# Dual6X03.net
KiCad netlist of a schematic drawn in EAGLE
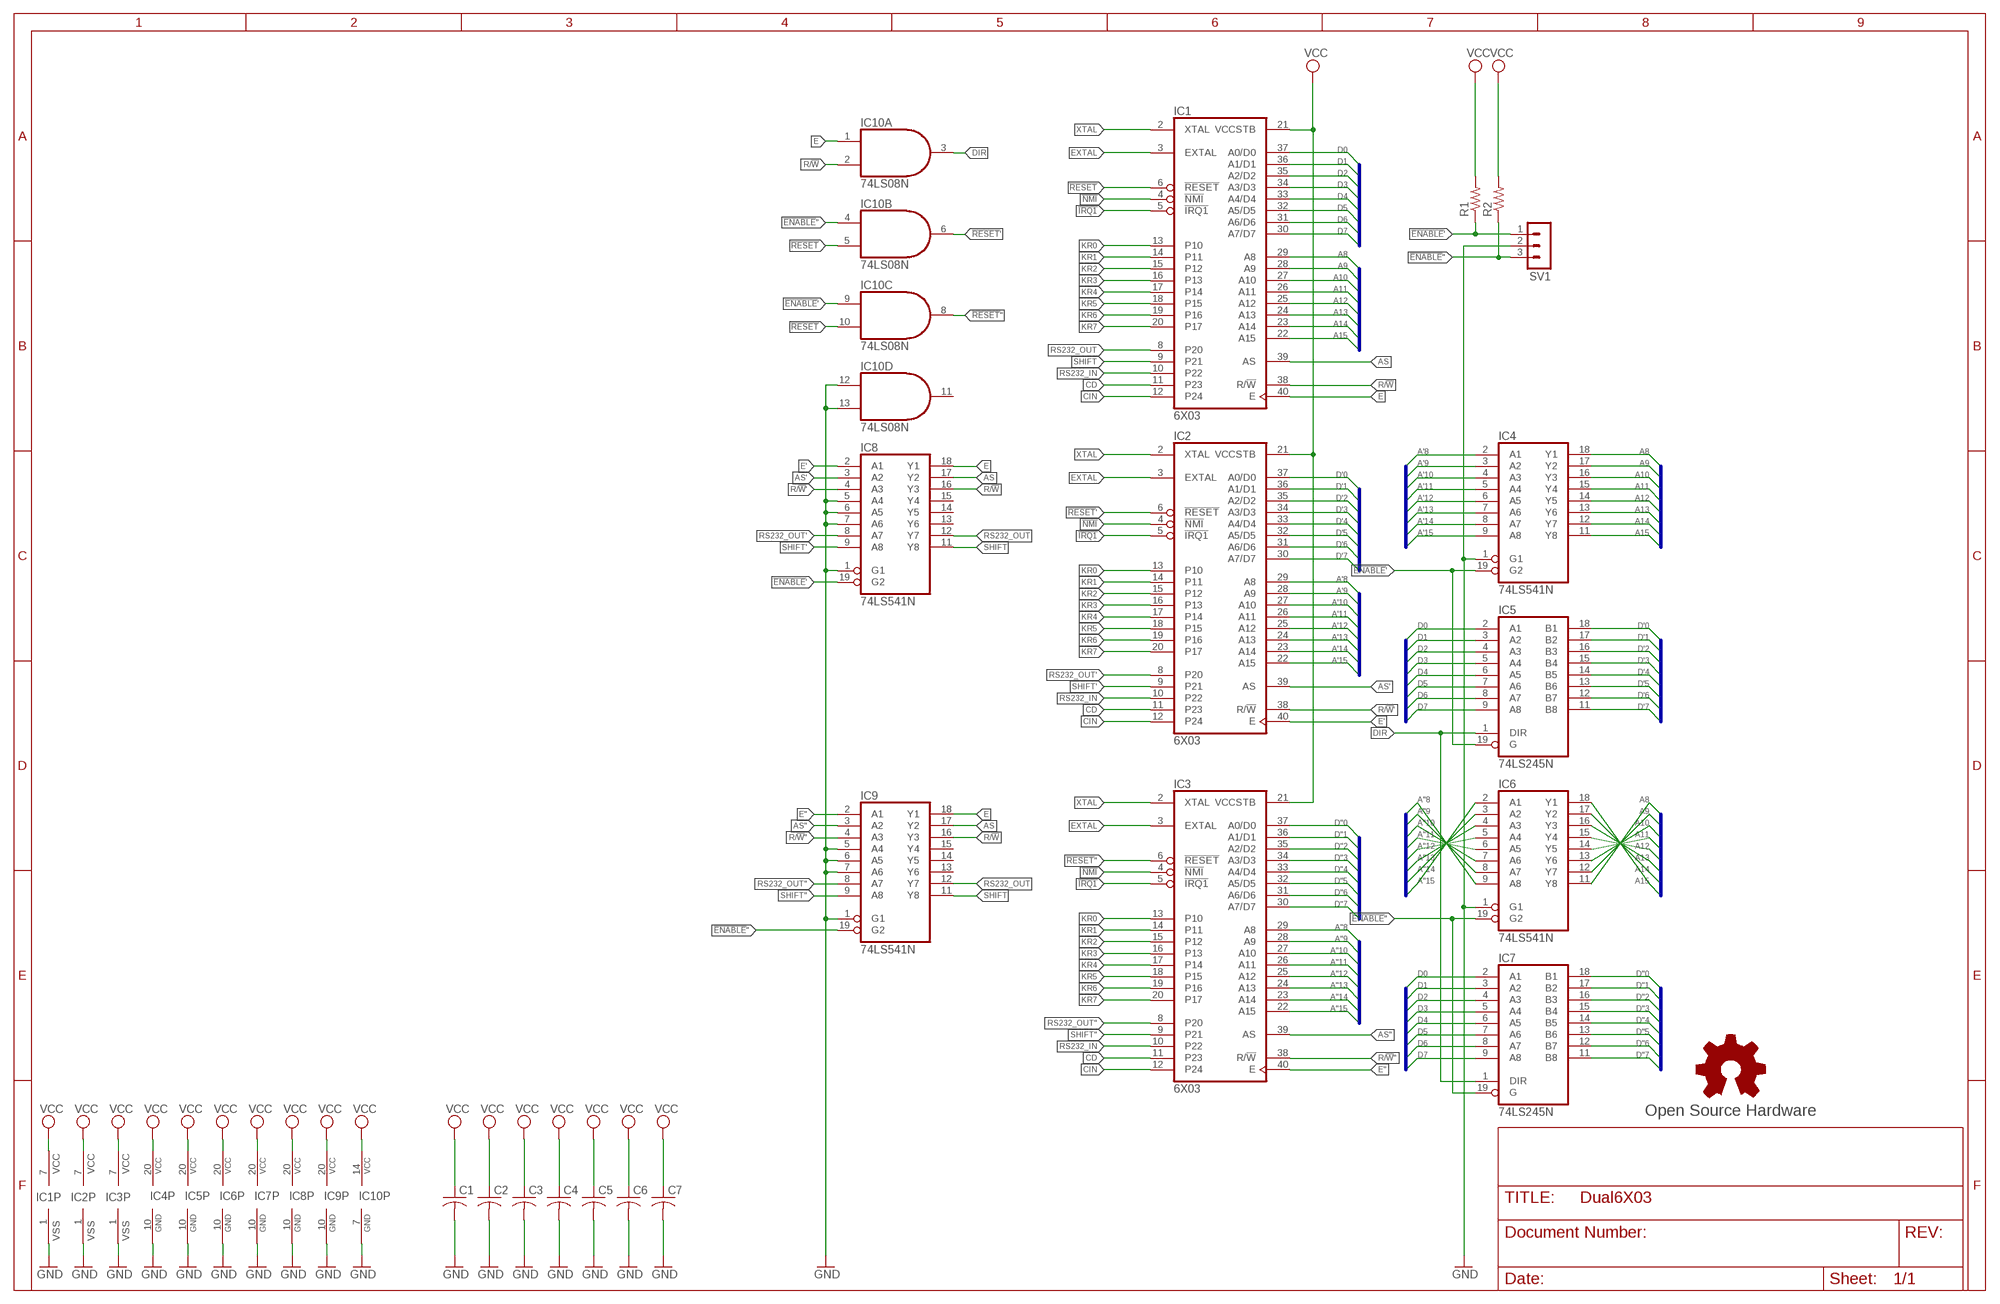
[diagram p0: schematic, sheet 1]

(export (version "E")
  (design (tool "Eeschema 10.0.6"))
  (components
    (comp (ref "C1")
      (value "C-US025-025X050")
      (footprint "eagle-import:C025-025X050")
      (libsource (lib "eagle-import") (part "C-US025-025X050"))
    )
    (comp (ref "C2")
      (value "C-US025-025X050")
      (footprint "eagle-import:C025-025X050")
      (libsource (lib "eagle-import") (part "C-US025-025X050"))
    )
    (comp (ref "C3")
      (value "C-US025-025X050")
      (footprint "eagle-import:C025-025X050")
      (libsource (lib "eagle-import") (part "C-US025-025X050"))
    )
    (comp (ref "C4")
      (value "C-US025-025X050")
      (footprint "eagle-import:C025-025X050")
      (libsource (lib "eagle-import") (part "C-US025-025X050"))
    )
    (comp (ref "C5")
      (value "C-US025-025X050")
      (footprint "eagle-import:C025-025X050")
      (libsource (lib "eagle-import") (part "C-US025-025X050"))
    )
    (comp (ref "C6")
      (value "C-US025-025X050")
      (footprint "eagle-import:C025-025X050")
      (libsource (lib "eagle-import") (part "C-US025-025X050"))
    )
    (comp (ref "C7")
      (value "C-US025-025X050")
      (footprint "eagle-import:C025-025X050")
      (libsource (lib "eagle-import") (part "C-US025-025X050"))
    )
    (comp (ref "GOLD_ORB_SM1")
      (value "Open Source Hardware")
      (footprint "eagle-import:OSHW_8MM")
      (libsource (lib "eagle-import") (part "OSHWLOGOLOGO8MM"))
    )
    (comp (ref "IC1")
      (value "6X03")
      (footprint "eagle-import:DIL40-ROUNDPAD")
      (libsource (lib "eagle-import") (part "6801EMR"))
    )
    (comp (ref "IC2")
      (value "6X03")
      (footprint "eagle-import:DIL40-ROUNDPAD")
      (libsource (lib "eagle-import") (part "6801EMR"))
    )
    (comp (ref "IC3")
      (value "6X03")
      (footprint "eagle-import:DIL40-ROUNDPAD")
      (libsource (lib "eagle-import") (part "6801EMR"))
    )
    (comp (ref "IC4")
      (value "74LS541N")
      (footprint "eagle-import:DIL20")
      (libsource (lib "eagle-import") (part "74541NLS"))
    )
    (comp (ref "IC5")
      (value "74LS245N")
      (footprint "eagle-import:DIL20")
      (libsource (lib "eagle-import") (part "74245NLS"))
    )
    (comp (ref "IC6")
      (value "74LS541N")
      (footprint "eagle-import:DIL20")
      (libsource (lib "eagle-import") (part "74541NLS"))
    )
    (comp (ref "IC7")
      (value "74LS245N")
      (footprint "eagle-import:DIL20")
      (libsource (lib "eagle-import") (part "74245NLS"))
    )
    (comp (ref "IC8")
      (value "74LS541N")
      (footprint "eagle-import:DIL20")
      (libsource (lib "eagle-import") (part "74541NLS"))
    )
    (comp (ref "IC9")
      (value "74LS541N")
      (footprint "eagle-import:DIL20")
      (libsource (lib "eagle-import") (part "74541NLS"))
    )
    (comp (ref "IC10")
      (value "74LS08N")
      (footprint "eagle-import:DIL14")
      (libsource (lib "eagle-import") (part "7408NLS"))
    )
    (comp (ref "R1")
      (value "R-US_0204/2V")
      (footprint "eagle-import:0204V")
      (libsource (lib "eagle-import") (part "R-US_0204/2V"))
    )
    (comp (ref "R2")
      (value "R-US_0204/2V")
      (footprint "eagle-import:0204V")
      (libsource (lib "eagle-import") (part "R-US_0204/2V"))
    )
    (comp (ref "SV1")
      (value "MA03-1")
      (footprint "eagle-import:MA03-1")
      (libsource (lib "eagle-import") (part "MA03-1"))
    )
  )
  (nets
    (net (code "1") (name "/A''8") (class "Default")
      (node (ref "IC3") (pin "29") (pinfunction "A8_29") (pintype "bidirectional"))
      (node (ref "IC6") (pin "9") (pinfunction "A8_9") (pintype "input"))
    )
    (net (code "2") (name "/A''9") (class "Default")
      (node (ref "IC3") (pin "28") (pinfunction "A9_28") (pintype "bidirectional"))
      (node (ref "IC6") (pin "8") (pinfunction "A7_8") (pintype "input"))
    )
    (net (code "3") (name "/A''10") (class "Default")
      (node (ref "IC3") (pin "27") (pinfunction "A10_27") (pintype "bidirectional"))
      (node (ref "IC6") (pin "7") (pinfunction "A6_7") (pintype "input"))
    )
    (net (code "4") (name "/A''11") (class "Default")
      (node (ref "IC3") (pin "26") (pinfunction "A11_26") (pintype "bidirectional"))
      (node (ref "IC6") (pin "6") (pinfunction "A5_6") (pintype "input"))
    )
    (net (code "5") (name "/A''12") (class "Default")
      (node (ref "IC3") (pin "25") (pinfunction "A12_25") (pintype "bidirectional"))
      (node (ref "IC6") (pin "5") (pinfunction "A4_5") (pintype "input"))
    )
    (net (code "6") (name "/A''13") (class "Default")
      (node (ref "IC3") (pin "24") (pinfunction "A13_24") (pintype "bidirectional"))
      (node (ref "IC6") (pin "4") (pinfunction "A3_4") (pintype "input"))
    )
    (net (code "7") (name "/A''14") (class "Default")
      (node (ref "IC3") (pin "23") (pinfunction "A14_23") (pintype "bidirectional"))
      (node (ref "IC6") (pin "3") (pinfunction "A2_3") (pintype "input"))
    )
    (net (code "8") (name "/A''15") (class "Default")
      (node (ref "IC3") (pin "22") (pinfunction "A15_22") (pintype "bidirectional"))
      (node (ref "IC6") (pin "2") (pinfunction "A1_2") (pintype "input"))
    )
    (net (code "9") (name "/A'8") (class "Default")
      (node (ref "IC2") (pin "29") (pinfunction "A8_29") (pintype "bidirectional"))
      (node (ref "IC4") (pin "2") (pinfunction "A1_2") (pintype "input"))
    )
    (net (code "10") (name "/A'9") (class "Default")
      (node (ref "IC2") (pin "28") (pinfunction "A9_28") (pintype "bidirectional"))
      (node (ref "IC4") (pin "3") (pinfunction "A2_3") (pintype "input"))
    )
    (net (code "11") (name "/A'10") (class "Default")
      (node (ref "IC2") (pin "27") (pinfunction "A10_27") (pintype "bidirectional"))
      (node (ref "IC4") (pin "4") (pinfunction "A3_4") (pintype "input"))
    )
    (net (code "12") (name "/A'11") (class "Default")
      (node (ref "IC2") (pin "26") (pinfunction "A11_26") (pintype "bidirectional"))
      (node (ref "IC4") (pin "5") (pinfunction "A4_5") (pintype "input"))
    )
    (net (code "13") (name "/A'12") (class "Default")
      (node (ref "IC2") (pin "25") (pinfunction "A12_25") (pintype "bidirectional"))
      (node (ref "IC4") (pin "6") (pinfunction "A5_6") (pintype "input"))
    )
    (net (code "14") (name "/A'13") (class "Default")
      (node (ref "IC2") (pin "24") (pinfunction "A13_24") (pintype "bidirectional"))
      (node (ref "IC4") (pin "7") (pinfunction "A6_7") (pintype "input"))
    )
    (net (code "15") (name "/A'14") (class "Default")
      (node (ref "IC2") (pin "23") (pinfunction "A14_23") (pintype "bidirectional"))
      (node (ref "IC4") (pin "8") (pinfunction "A7_8") (pintype "input"))
    )
    (net (code "16") (name "/A'15") (class "Default")
      (node (ref "IC2") (pin "22") (pinfunction "A15_22") (pintype "bidirectional"))
      (node (ref "IC4") (pin "9") (pinfunction "A8_9") (pintype "input"))
    )
    (net (code "17") (name "/A8") (class "Default")
      (node (ref "IC1") (pin "29") (pinfunction "A8_29") (pintype "bidirectional"))
      (node (ref "IC4") (pin "18") (pinfunction "Y1_18") (pintype "tri_state"))
      (node (ref "IC6") (pin "11") (pinfunction "Y8_11") (pintype "tri_state"))
    )
    (net (code "18") (name "/A9") (class "Default")
      (node (ref "IC1") (pin "28") (pinfunction "A9_28") (pintype "bidirectional"))
      (node (ref "IC4") (pin "17") (pinfunction "Y2_17") (pintype "tri_state"))
      (node (ref "IC6") (pin "12") (pinfunction "Y7_12") (pintype "tri_state"))
    )
    (net (code "19") (name "/A10") (class "Default")
      (node (ref "IC1") (pin "27") (pinfunction "A10_27") (pintype "bidirectional"))
      (node (ref "IC4") (pin "16") (pinfunction "Y3_16") (pintype "tri_state"))
      (node (ref "IC6") (pin "13") (pinfunction "Y6_13") (pintype "tri_state"))
    )
    (net (code "20") (name "/A11") (class "Default")
      (node (ref "IC1") (pin "26") (pinfunction "A11_26") (pintype "bidirectional"))
      (node (ref "IC4") (pin "15") (pinfunction "Y4_15") (pintype "tri_state"))
      (node (ref "IC6") (pin "14") (pinfunction "Y5_14") (pintype "tri_state"))
    )
    (net (code "21") (name "/A12") (class "Default")
      (node (ref "IC1") (pin "25") (pinfunction "A12_25") (pintype "bidirectional"))
      (node (ref "IC4") (pin "14") (pinfunction "Y5_14") (pintype "tri_state"))
      (node (ref "IC6") (pin "15") (pinfunction "Y4_15") (pintype "tri_state"))
    )
    (net (code "22") (name "/A13") (class "Default")
      (node (ref "IC1") (pin "24") (pinfunction "A13_24") (pintype "bidirectional"))
      (node (ref "IC4") (pin "13") (pinfunction "Y6_13") (pintype "tri_state"))
      (node (ref "IC6") (pin "16") (pinfunction "Y3_16") (pintype "tri_state"))
    )
    (net (code "23") (name "/A14") (class "Default")
      (node (ref "IC1") (pin "23") (pinfunction "A14_23") (pintype "bidirectional"))
      (node (ref "IC4") (pin "12") (pinfunction "Y7_12") (pintype "tri_state"))
      (node (ref "IC6") (pin "17") (pinfunction "Y2_17") (pintype "tri_state"))
    )
    (net (code "24") (name "/A15") (class "Default")
      (node (ref "IC1") (pin "22") (pinfunction "A15_22") (pintype "bidirectional"))
      (node (ref "IC4") (pin "11") (pinfunction "Y8_11") (pintype "tri_state"))
      (node (ref "IC6") (pin "18") (pinfunction "Y1_18") (pintype "tri_state"))
    )
    (net (code "25") (name "/D''0") (class "Default")
      (node (ref "IC3") (pin "37") (pinfunction "A0/D0_37") (pintype "bidirectional"))
      (node (ref "IC7") (pin "18") (pinfunction "B1_18") (pintype "bidirectional"))
    )
    (net (code "26") (name "/D''1") (class "Default")
      (node (ref "IC3") (pin "36") (pinfunction "A1/D1_36") (pintype "bidirectional"))
      (node (ref "IC7") (pin "17") (pinfunction "B2_17") (pintype "bidirectional"))
    )
    (net (code "27") (name "/D''2") (class "Default")
      (node (ref "IC3") (pin "35") (pinfunction "A2/D2_35") (pintype "bidirectional"))
      (node (ref "IC7") (pin "16") (pinfunction "B3_16") (pintype "bidirectional"))
    )
    (net (code "28") (name "/D''3") (class "Default")
      (node (ref "IC3") (pin "34") (pinfunction "A3/D3_34") (pintype "bidirectional"))
      (node (ref "IC7") (pin "15") (pinfunction "B4_15") (pintype "bidirectional"))
    )
    (net (code "29") (name "/D''4") (class "Default")
      (node (ref "IC3") (pin "33") (pinfunction "A4/D4_33") (pintype "bidirectional"))
      (node (ref "IC7") (pin "14") (pinfunction "B5_14") (pintype "bidirectional"))
    )
    (net (code "30") (name "/D''5") (class "Default")
      (node (ref "IC3") (pin "32") (pinfunction "A5/D5_32") (pintype "bidirectional"))
      (node (ref "IC7") (pin "13") (pinfunction "B6_13") (pintype "bidirectional"))
    )
    (net (code "31") (name "/D''6") (class "Default")
      (node (ref "IC3") (pin "31") (pinfunction "A6/D6_31") (pintype "bidirectional"))
      (node (ref "IC7") (pin "12") (pinfunction "B7_12") (pintype "bidirectional"))
    )
    (net (code "32") (name "/D''7") (class "Default")
      (node (ref "IC3") (pin "30") (pinfunction "A7/D7_30") (pintype "bidirectional"))
      (node (ref "IC7") (pin "11") (pinfunction "B8_11") (pintype "bidirectional"))
    )
    (net (code "33") (name "/D'0") (class "Default")
      (node (ref "IC2") (pin "37") (pinfunction "A0/D0_37") (pintype "bidirectional"))
      (node (ref "IC5") (pin "18") (pinfunction "B1_18") (pintype "bidirectional"))
    )
    (net (code "34") (name "/D'1") (class "Default")
      (node (ref "IC2") (pin "36") (pinfunction "A1/D1_36") (pintype "bidirectional"))
      (node (ref "IC5") (pin "17") (pinfunction "B2_17") (pintype "bidirectional"))
    )
    (net (code "35") (name "/D'2") (class "Default")
      (node (ref "IC2") (pin "35") (pinfunction "A2/D2_35") (pintype "bidirectional"))
      (node (ref "IC5") (pin "16") (pinfunction "B3_16") (pintype "bidirectional"))
    )
    (net (code "36") (name "/D'3") (class "Default")
      (node (ref "IC2") (pin "34") (pinfunction "A3/D3_34") (pintype "bidirectional"))
      (node (ref "IC5") (pin "15") (pinfunction "B4_15") (pintype "bidirectional"))
    )
    (net (code "37") (name "/D'4") (class "Default")
      (node (ref "IC2") (pin "33") (pinfunction "A4/D4_33") (pintype "bidirectional"))
      (node (ref "IC5") (pin "14") (pinfunction "B5_14") (pintype "bidirectional"))
    )
    (net (code "38") (name "/D'5") (class "Default")
      (node (ref "IC2") (pin "32") (pinfunction "A5/D5_32") (pintype "bidirectional"))
      (node (ref "IC5") (pin "13") (pinfunction "B6_13") (pintype "bidirectional"))
    )
    (net (code "39") (name "/D'6") (class "Default")
      (node (ref "IC2") (pin "31") (pinfunction "A6/D6_31") (pintype "bidirectional"))
      (node (ref "IC5") (pin "12") (pinfunction "B7_12") (pintype "bidirectional"))
    )
    (net (code "40") (name "/D'7") (class "Default")
      (node (ref "IC2") (pin "30") (pinfunction "A7/D7_30") (pintype "bidirectional"))
      (node (ref "IC5") (pin "11") (pinfunction "B8_11") (pintype "bidirectional"))
    )
    (net (code "41") (name "/D0") (class "Default")
      (node (ref "IC1") (pin "37") (pinfunction "A0/D0_37") (pintype "bidirectional"))
      (node (ref "IC5") (pin "2") (pinfunction "A1_2") (pintype "bidirectional"))
      (node (ref "IC7") (pin "2") (pinfunction "A1_2") (pintype "bidirectional"))
    )
    (net (code "42") (name "/D1") (class "Default")
      (node (ref "IC1") (pin "36") (pinfunction "A1/D1_36") (pintype "bidirectional"))
      (node (ref "IC5") (pin "3") (pinfunction "A2_3") (pintype "bidirectional"))
      (node (ref "IC7") (pin "3") (pinfunction "A2_3") (pintype "bidirectional"))
    )
    (net (code "43") (name "/D2") (class "Default")
      (node (ref "IC1") (pin "35") (pinfunction "A2/D2_35") (pintype "bidirectional"))
      (node (ref "IC5") (pin "4") (pinfunction "A3_4") (pintype "bidirectional"))
      (node (ref "IC7") (pin "4") (pinfunction "A3_4") (pintype "bidirectional"))
    )
    (net (code "44") (name "/D3") (class "Default")
      (node (ref "IC1") (pin "34") (pinfunction "A3/D3_34") (pintype "bidirectional"))
      (node (ref "IC5") (pin "5") (pinfunction "A4_5") (pintype "bidirectional"))
      (node (ref "IC7") (pin "5") (pinfunction "A4_5") (pintype "bidirectional"))
    )
    (net (code "45") (name "/D4") (class "Default")
      (node (ref "IC1") (pin "33") (pinfunction "A4/D4_33") (pintype "bidirectional"))
      (node (ref "IC5") (pin "6") (pinfunction "A5_6") (pintype "bidirectional"))
      (node (ref "IC7") (pin "6") (pinfunction "A5_6") (pintype "bidirectional"))
    )
    (net (code "46") (name "/D5") (class "Default")
      (node (ref "IC1") (pin "32") (pinfunction "A5/D5_32") (pintype "bidirectional"))
      (node (ref "IC5") (pin "7") (pinfunction "A6_7") (pintype "bidirectional"))
      (node (ref "IC7") (pin "7") (pinfunction "A6_7") (pintype "bidirectional"))
    )
    (net (code "47") (name "/D6") (class "Default")
      (node (ref "IC1") (pin "31") (pinfunction "A6/D6_31") (pintype "bidirectional"))
      (node (ref "IC5") (pin "8") (pinfunction "A7_8") (pintype "bidirectional"))
      (node (ref "IC7") (pin "8") (pinfunction "A7_8") (pintype "bidirectional"))
    )
    (net (code "48") (name "/D7") (class "Default")
      (node (ref "IC1") (pin "30") (pinfunction "A7/D7_30") (pintype "bidirectional"))
      (node (ref "IC5") (pin "9") (pinfunction "A8_9") (pintype "bidirectional"))
      (node (ref "IC7") (pin "9") (pinfunction "A8_9") (pintype "bidirectional"))
    )
    (net (code "49") (name "/R{slash}~{W}") (class "Default")
      (node (ref "IC1") (pin "38") (pinfunction "R/~{W}_38") (pintype "output"))
      (node (ref "IC10") (pin "2") (pinfunction "I1_2") (pintype "input"))
      (node (ref "IC8") (pin "16") (pinfunction "Y3_16") (pintype "tri_state"))
      (node (ref "IC9") (pin "16") (pinfunction "Y3_16") (pintype "tri_state"))
    )
    (net (code "50") (name "/R{slash}~{W}'") (class "Default")
      (node (ref "IC2") (pin "38") (pinfunction "R/~{W}_38") (pintype "output"))
      (node (ref "IC8") (pin "4") (pinfunction "A3_4") (pintype "input"))
    )
    (net (code "51") (name "/R{slash}~{W}''") (class "Default")
      (node (ref "IC3") (pin "38") (pinfunction "R/~{W}_38") (pintype "output"))
      (node (ref "IC9") (pin "4") (pinfunction "A3_4") (pintype "input"))
    )
    (net (code "52") (name "/~{ENABLE}'") (class "Default")
      (node (ref "IC10") (pin "9") (pinfunction "I0_9") (pintype "input"))
      (node (ref "IC4") (pin "19") (pinfunction "G2_19") (pintype "input"))
      (node (ref "IC5") (pin "19") (pinfunction "G_19") (pintype "input"))
      (node (ref "IC8") (pin "19") (pinfunction "G2_19") (pintype "input"))
      (node (ref "R1") (pin "1") (pinfunction "1_1") (pintype "passive"))
      (node (ref "SV1") (pin "1") (pinfunction "1_1") (pintype "passive"))
    )
    (net (code "53") (name "/~{ENABLE}''") (class "Default")
      (node (ref "IC10") (pin "4") (pinfunction "I0_4") (pintype "input"))
      (node (ref "IC6") (pin "19") (pinfunction "G2_19") (pintype "input"))
      (node (ref "IC7") (pin "19") (pinfunction "G_19") (pintype "input"))
      (node (ref "IC9") (pin "19") (pinfunction "G2_19") (pintype "input"))
      (node (ref "R2") (pin "1") (pinfunction "1_1") (pintype "passive"))
      (node (ref "SV1") (pin "3") (pinfunction "3_3") (pintype "passive"))
    )
    (net (code "54") (name "/~{IRQ1}") (class "Default")
      (node (ref "IC1") (pin "5") (pinfunction "~{IRQ1}_5") (pintype "input"))
      (node (ref "IC2") (pin "5") (pinfunction "~{IRQ1}_5") (pintype "input"))
      (node (ref "IC3") (pin "5") (pinfunction "~{IRQ1}_5") (pintype "input"))
    )
    (net (code "55") (name "/~{NMI}") (class "Default")
      (node (ref "IC1") (pin "4") (pinfunction "~{NMI}_4") (pintype "input"))
      (node (ref "IC2") (pin "4") (pinfunction "~{NMI}_4") (pintype "input"))
      (node (ref "IC3") (pin "4") (pinfunction "~{NMI}_4") (pintype "input"))
    )
    (net (code "56") (name "/~{RESET}") (class "Default")
      (node (ref "IC1") (pin "6") (pinfunction "~{RESET}_6") (pintype "input"))
      (node (ref "IC10") (pin "10") (pinfunction "I1_10") (pintype "input"))
      (node (ref "IC10") (pin "5") (pinfunction "I1_5") (pintype "input"))
    )
    (net (code "57") (name "/~{RESET}'") (class "Default")
      (node (ref "IC10") (pin "6") (pinfunction "O_6") (pintype "output"))
      (node (ref "IC2") (pin "6") (pinfunction "~{RESET}_6") (pintype "input"))
    )
    (net (code "58") (name "/~{RESET}''") (class "Default")
      (node (ref "IC10") (pin "8") (pinfunction "O_8") (pintype "output"))
      (node (ref "IC3") (pin "6") (pinfunction "~{RESET}_6") (pintype "input"))
    )
    (net (code "59") (name "AS") (class "Default")
      (node (ref "IC1") (pin "39") (pinfunction "AS_39") (pintype "bidirectional"))
      (node (ref "IC8") (pin "17") (pinfunction "Y2_17") (pintype "tri_state"))
      (node (ref "IC9") (pin "17") (pinfunction "Y2_17") (pintype "tri_state"))
    )
    (net (code "60") (name "AS'") (class "Default")
      (node (ref "IC2") (pin "39") (pinfunction "AS_39") (pintype "bidirectional"))
      (node (ref "IC8") (pin "3") (pinfunction "A2_3") (pintype "input"))
    )
    (net (code "61") (name "AS''") (class "Default")
      (node (ref "IC3") (pin "39") (pinfunction "AS_39") (pintype "bidirectional"))
      (node (ref "IC9") (pin "3") (pinfunction "A2_3") (pintype "input"))
    )
    (net (code "62") (name "CD") (class "Default")
      (node (ref "IC1") (pin "11") (pinfunction "P23_11") (pintype "bidirectional"))
      (node (ref "IC2") (pin "11") (pinfunction "P23_11") (pintype "bidirectional"))
      (node (ref "IC3") (pin "11") (pinfunction "P23_11") (pintype "bidirectional"))
    )
    (net (code "63") (name "CIN") (class "Default")
      (node (ref "IC1") (pin "12") (pinfunction "P24_12") (pintype "bidirectional"))
      (node (ref "IC2") (pin "12") (pinfunction "P24_12") (pintype "bidirectional"))
      (node (ref "IC3") (pin "12") (pinfunction "P24_12") (pintype "bidirectional"))
    )
    (net (code "64") (name "DIR") (class "Default")
      (node (ref "IC10") (pin "3") (pinfunction "O_3") (pintype "output"))
      (node (ref "IC5") (pin "1") (pinfunction "DIR_1") (pintype "input"))
      (node (ref "IC7") (pin "1") (pinfunction "DIR_1") (pintype "input"))
    )
    (net (code "65") (name "E") (class "Default")
      (node (ref "IC1") (pin "40") (pinfunction "E_40") (pintype "output"))
      (node (ref "IC10") (pin "1") (pinfunction "I0_1") (pintype "input"))
      (node (ref "IC8") (pin "18") (pinfunction "Y1_18") (pintype "tri_state"))
      (node (ref "IC9") (pin "18") (pinfunction "Y1_18") (pintype "tri_state"))
    )
    (net (code "66") (name "E'") (class "Default")
      (node (ref "IC2") (pin "40") (pinfunction "E_40") (pintype "output"))
      (node (ref "IC8") (pin "2") (pinfunction "A1_2") (pintype "input"))
    )
    (net (code "67") (name "E''") (class "Default")
      (node (ref "IC3") (pin "40") (pinfunction "E_40") (pintype "output"))
      (node (ref "IC9") (pin "2") (pinfunction "A1_2") (pintype "input"))
    )
    (net (code "68") (name "EXTAL") (class "Default")
      (node (ref "IC1") (pin "3") (pinfunction "EXTAL_3") (pintype "input"))
      (node (ref "IC2") (pin "3") (pinfunction "EXTAL_3") (pintype "input"))
      (node (ref "IC3") (pin "3") (pinfunction "EXTAL_3") (pintype "input"))
    )
    (net (code "69") (name "GND") (class "Default")
      (node (ref "C1") (pin "2") (pinfunction "2_2") (pintype "passive"))
      (node (ref "C2") (pin "2") (pinfunction "2_2") (pintype "passive"))
      (node (ref "C3") (pin "2") (pinfunction "2_2") (pintype "passive"))
      (node (ref "C4") (pin "2") (pinfunction "2_2") (pintype "passive"))
      (node (ref "C5") (pin "2") (pinfunction "2_2") (pintype "passive"))
      (node (ref "C6") (pin "2") (pinfunction "2_2") (pintype "passive"))
      (node (ref "C7") (pin "2") (pinfunction "2_2") (pintype "passive"))
      (node (ref "IC1") (pin "1") (pinfunction "VSS_1") (pintype "power_in"))
      (node (ref "IC10") (pin "12") (pinfunction "I0_12") (pintype "input"))
      (node (ref "IC10") (pin "13") (pinfunction "I1_13") (pintype "input"))
      (node (ref "IC10") (pin "7") (pinfunction "GND_7") (pintype "power_in"))
      (node (ref "IC2") (pin "1") (pinfunction "VSS_1") (pintype "power_in"))
      (node (ref "IC3") (pin "1") (pinfunction "VSS_1") (pintype "power_in"))
      (node (ref "IC4") (pin "1") (pinfunction "G1_1") (pintype "input"))
      (node (ref "IC4") (pin "10") (pinfunction "GND_10") (pintype "power_in"))
      (node (ref "IC5") (pin "10") (pinfunction "GND_10") (pintype "power_in"))
      (node (ref "IC6") (pin "1") (pinfunction "G1_1") (pintype "input"))
      (node (ref "IC6") (pin "10") (pinfunction "GND_10") (pintype "power_in"))
      (node (ref "IC7") (pin "10") (pinfunction "GND_10") (pintype "power_in"))
      (node (ref "IC8") (pin "1") (pinfunction "G1_1") (pintype "input"))
      (node (ref "IC8") (pin "10") (pinfunction "GND_10") (pintype "power_in"))
      (node (ref "IC8") (pin "5") (pinfunction "A4_5") (pintype "input"))
      (node (ref "IC8") (pin "6") (pinfunction "A5_6") (pintype "input"))
      (node (ref "IC8") (pin "7") (pinfunction "A6_7") (pintype "input"))
      (node (ref "IC9") (pin "1") (pinfunction "G1_1") (pintype "input"))
      (node (ref "IC9") (pin "10") (pinfunction "GND_10") (pintype "power_in"))
      (node (ref "IC9") (pin "5") (pinfunction "A4_5") (pintype "input"))
      (node (ref "IC9") (pin "6") (pinfunction "A5_6") (pintype "input"))
      (node (ref "IC9") (pin "7") (pinfunction "A6_7") (pintype "input"))
      (node (ref "SV1") (pin "2") (pinfunction "2_2") (pintype "passive"))
    )
    (net (code "70") (name "KR0") (class "Default")
      (node (ref "IC1") (pin "13") (pinfunction "P10_13") (pintype "bidirectional"))
      (node (ref "IC2") (pin "13") (pinfunction "P10_13") (pintype "bidirectional"))
      (node (ref "IC3") (pin "13") (pinfunction "P10_13") (pintype "bidirectional"))
    )
    (net (code "71") (name "KR1") (class "Default")
      (node (ref "IC1") (pin "14") (pinfunction "P11_14") (pintype "bidirectional"))
      (node (ref "IC2") (pin "14") (pinfunction "P11_14") (pintype "bidirectional"))
      (node (ref "IC3") (pin "14") (pinfunction "P11_14") (pintype "bidirectional"))
    )
    (net (code "72") (name "KR2") (class "Default")
      (node (ref "IC1") (pin "15") (pinfunction "P12_15") (pintype "bidirectional"))
      (node (ref "IC2") (pin "15") (pinfunction "P12_15") (pintype "bidirectional"))
      (node (ref "IC3") (pin "15") (pinfunction "P12_15") (pintype "bidirectional"))
    )
    (net (code "73") (name "KR3") (class "Default")
      (node (ref "IC1") (pin "16") (pinfunction "P13_16") (pintype "bidirectional"))
      (node (ref "IC2") (pin "16") (pinfunction "P13_16") (pintype "bidirectional"))
      (node (ref "IC3") (pin "16") (pinfunction "P13_16") (pintype "bidirectional"))
    )
    (net (code "74") (name "KR4") (class "Default")
      (node (ref "IC1") (pin "17") (pinfunction "P14_17") (pintype "bidirectional"))
      (node (ref "IC2") (pin "17") (pinfunction "P14_17") (pintype "bidirectional"))
      (node (ref "IC3") (pin "17") (pinfunction "P14_17") (pintype "bidirectional"))
    )
    (net (code "75") (name "KR5") (class "Default")
      (node (ref "IC1") (pin "18") (pinfunction "P15_18") (pintype "bidirectional"))
      (node (ref "IC2") (pin "18") (pinfunction "P15_18") (pintype "bidirectional"))
      (node (ref "IC3") (pin "18") (pinfunction "P15_18") (pintype "bidirectional"))
    )
    (net (code "76") (name "KR6") (class "Default")
      (node (ref "IC1") (pin "19") (pinfunction "P16_19") (pintype "bidirectional"))
      (node (ref "IC2") (pin "19") (pinfunction "P16_19") (pintype "bidirectional"))
      (node (ref "IC3") (pin "19") (pinfunction "P16_19") (pintype "bidirectional"))
    )
    (net (code "77") (name "KR7") (class "Default")
      (node (ref "IC1") (pin "20") (pinfunction "P17_20") (pintype "bidirectional"))
      (node (ref "IC2") (pin "20") (pinfunction "P17_20") (pintype "bidirectional"))
      (node (ref "IC3") (pin "20") (pinfunction "P17_20") (pintype "bidirectional"))
    )
    (net (code "78") (name "RS232_IN") (class "Default")
      (node (ref "IC1") (pin "10") (pinfunction "P22_10") (pintype "bidirectional"))
      (node (ref "IC2") (pin "10") (pinfunction "P22_10") (pintype "bidirectional"))
      (node (ref "IC3") (pin "10") (pinfunction "P22_10") (pintype "bidirectional"))
    )
    (net (code "79") (name "RS232_OUT") (class "Default")
      (node (ref "IC1") (pin "8") (pinfunction "P20_8") (pintype "bidirectional"))
      (node (ref "IC8") (pin "12") (pinfunction "Y7_12") (pintype "tri_state"))
      (node (ref "IC9") (pin "12") (pinfunction "Y7_12") (pintype "tri_state"))
    )
    (net (code "80") (name "RS232_OUT'") (class "Default")
      (node (ref "IC2") (pin "8") (pinfunction "P20_8") (pintype "bidirectional"))
      (node (ref "IC8") (pin "8") (pinfunction "A7_8") (pintype "input"))
    )
    (net (code "81") (name "RS232_OUT''") (class "Default")
      (node (ref "IC3") (pin "8") (pinfunction "P20_8") (pintype "bidirectional"))
      (node (ref "IC9") (pin "8") (pinfunction "A7_8") (pintype "input"))
    )
    (net (code "82") (name "SHIFT") (class "Default")
      (node (ref "IC1") (pin "9") (pinfunction "P21_9") (pintype "bidirectional"))
      (node (ref "IC8") (pin "11") (pinfunction "Y8_11") (pintype "tri_state"))
      (node (ref "IC9") (pin "11") (pinfunction "Y8_11") (pintype "tri_state"))
    )
    (net (code "83") (name "SHIFT'") (class "Default")
      (node (ref "IC2") (pin "9") (pinfunction "P21_9") (pintype "bidirectional"))
      (node (ref "IC8") (pin "9") (pinfunction "A8_9") (pintype "input"))
    )
    (net (code "84") (name "SHIFT''") (class "Default")
      (node (ref "IC3") (pin "9") (pinfunction "P21_9") (pintype "bidirectional"))
      (node (ref "IC9") (pin "9") (pinfunction "A8_9") (pintype "input"))
    )
    (net (code "85") (name "VCC") (class "Default")
      (node (ref "C1") (pin "1") (pinfunction "1_1") (pintype "passive"))
      (node (ref "C2") (pin "1") (pinfunction "1_1") (pintype "passive"))
      (node (ref "C3") (pin "1") (pinfunction "1_1") (pintype "passive"))
      (node (ref "C4") (pin "1") (pinfunction "1_1") (pintype "passive"))
      (node (ref "C5") (pin "1") (pinfunction "1_1") (pintype "passive"))
      (node (ref "C6") (pin "1") (pinfunction "1_1") (pintype "passive"))
      (node (ref "C7") (pin "1") (pinfunction "1_1") (pintype "passive"))
      (node (ref "IC1") (pin "21") (pinfunction "VCCSTB_21") (pintype "input"))
      (node (ref "IC1") (pin "7") (pinfunction "VCC_7") (pintype "power_in"))
      (node (ref "IC10") (pin "14") (pinfunction "VCC_14") (pintype "power_in"))
      (node (ref "IC2") (pin "21") (pinfunction "VCCSTB_21") (pintype "input"))
      (node (ref "IC2") (pin "7") (pinfunction "VCC_7") (pintype "power_in"))
      (node (ref "IC3") (pin "21") (pinfunction "VCCSTB_21") (pintype "input"))
      (node (ref "IC3") (pin "7") (pinfunction "VCC_7") (pintype "power_in"))
      (node (ref "IC4") (pin "20") (pinfunction "VCC_20") (pintype "power_in"))
      (node (ref "IC5") (pin "20") (pinfunction "VCC_20") (pintype "power_in"))
      (node (ref "IC6") (pin "20") (pinfunction "VCC_20") (pintype "power_in"))
      (node (ref "IC7") (pin "20") (pinfunction "VCC_20") (pintype "power_in"))
      (node (ref "IC8") (pin "20") (pinfunction "VCC_20") (pintype "power_in"))
      (node (ref "IC9") (pin "20") (pinfunction "VCC_20") (pintype "power_in"))
      (node (ref "R1") (pin "2") (pinfunction "2_2") (pintype "passive"))
      (node (ref "R2") (pin "2") (pinfunction "2_2") (pintype "passive"))
    )
    (net (code "86") (name "XTAL") (class "Default")
      (node (ref "IC1") (pin "2") (pinfunction "XTAL_2") (pintype "input"))
      (node (ref "IC2") (pin "2") (pinfunction "XTAL_2") (pintype "input"))
      (node (ref "IC3") (pin "2") (pinfunction "XTAL_2") (pintype "input"))
    )
    (net (code "87") (name "unconnected-(IC8A-Y4-Pad15)") (class "Default")
      (node (ref "IC8") (pin "15") (pinfunction "Y4_15") (pintype "tri_state"))
    )
    (net (code "88") (name "unconnected-(IC8A-Y5-Pad14)") (class "Default")
      (node (ref "IC8") (pin "14") (pinfunction "Y5_14") (pintype "tri_state"))
    )
    (net (code "89") (name "unconnected-(IC8A-Y6-Pad13)") (class "Default")
      (node (ref "IC8") (pin "13") (pinfunction "Y6_13") (pintype "tri_state"))
    )
    (net (code "90") (name "unconnected-(IC9A-Y4-Pad15)") (class "Default")
      (node (ref "IC9") (pin "15") (pinfunction "Y4_15") (pintype "tri_state"))
    )
    (net (code "91") (name "unconnected-(IC9A-Y5-Pad14)") (class "Default")
      (node (ref "IC9") (pin "14") (pinfunction "Y5_14") (pintype "tri_state"))
    )
    (net (code "92") (name "unconnected-(IC9A-Y6-Pad13)") (class "Default")
      (node (ref "IC9") (pin "13") (pinfunction "Y6_13") (pintype "tri_state"))
    )
    (net (code "93") (name "unconnected-(IC10D-O-Pad11)") (class "Default")
      (node (ref "IC10") (pin "11") (pinfunction "O_11") (pintype "output"))
    )
  )
)
